# 6_Controller_A20_OUTPUT.net
KiCad netlist of a schematic drawn in Altium Designer
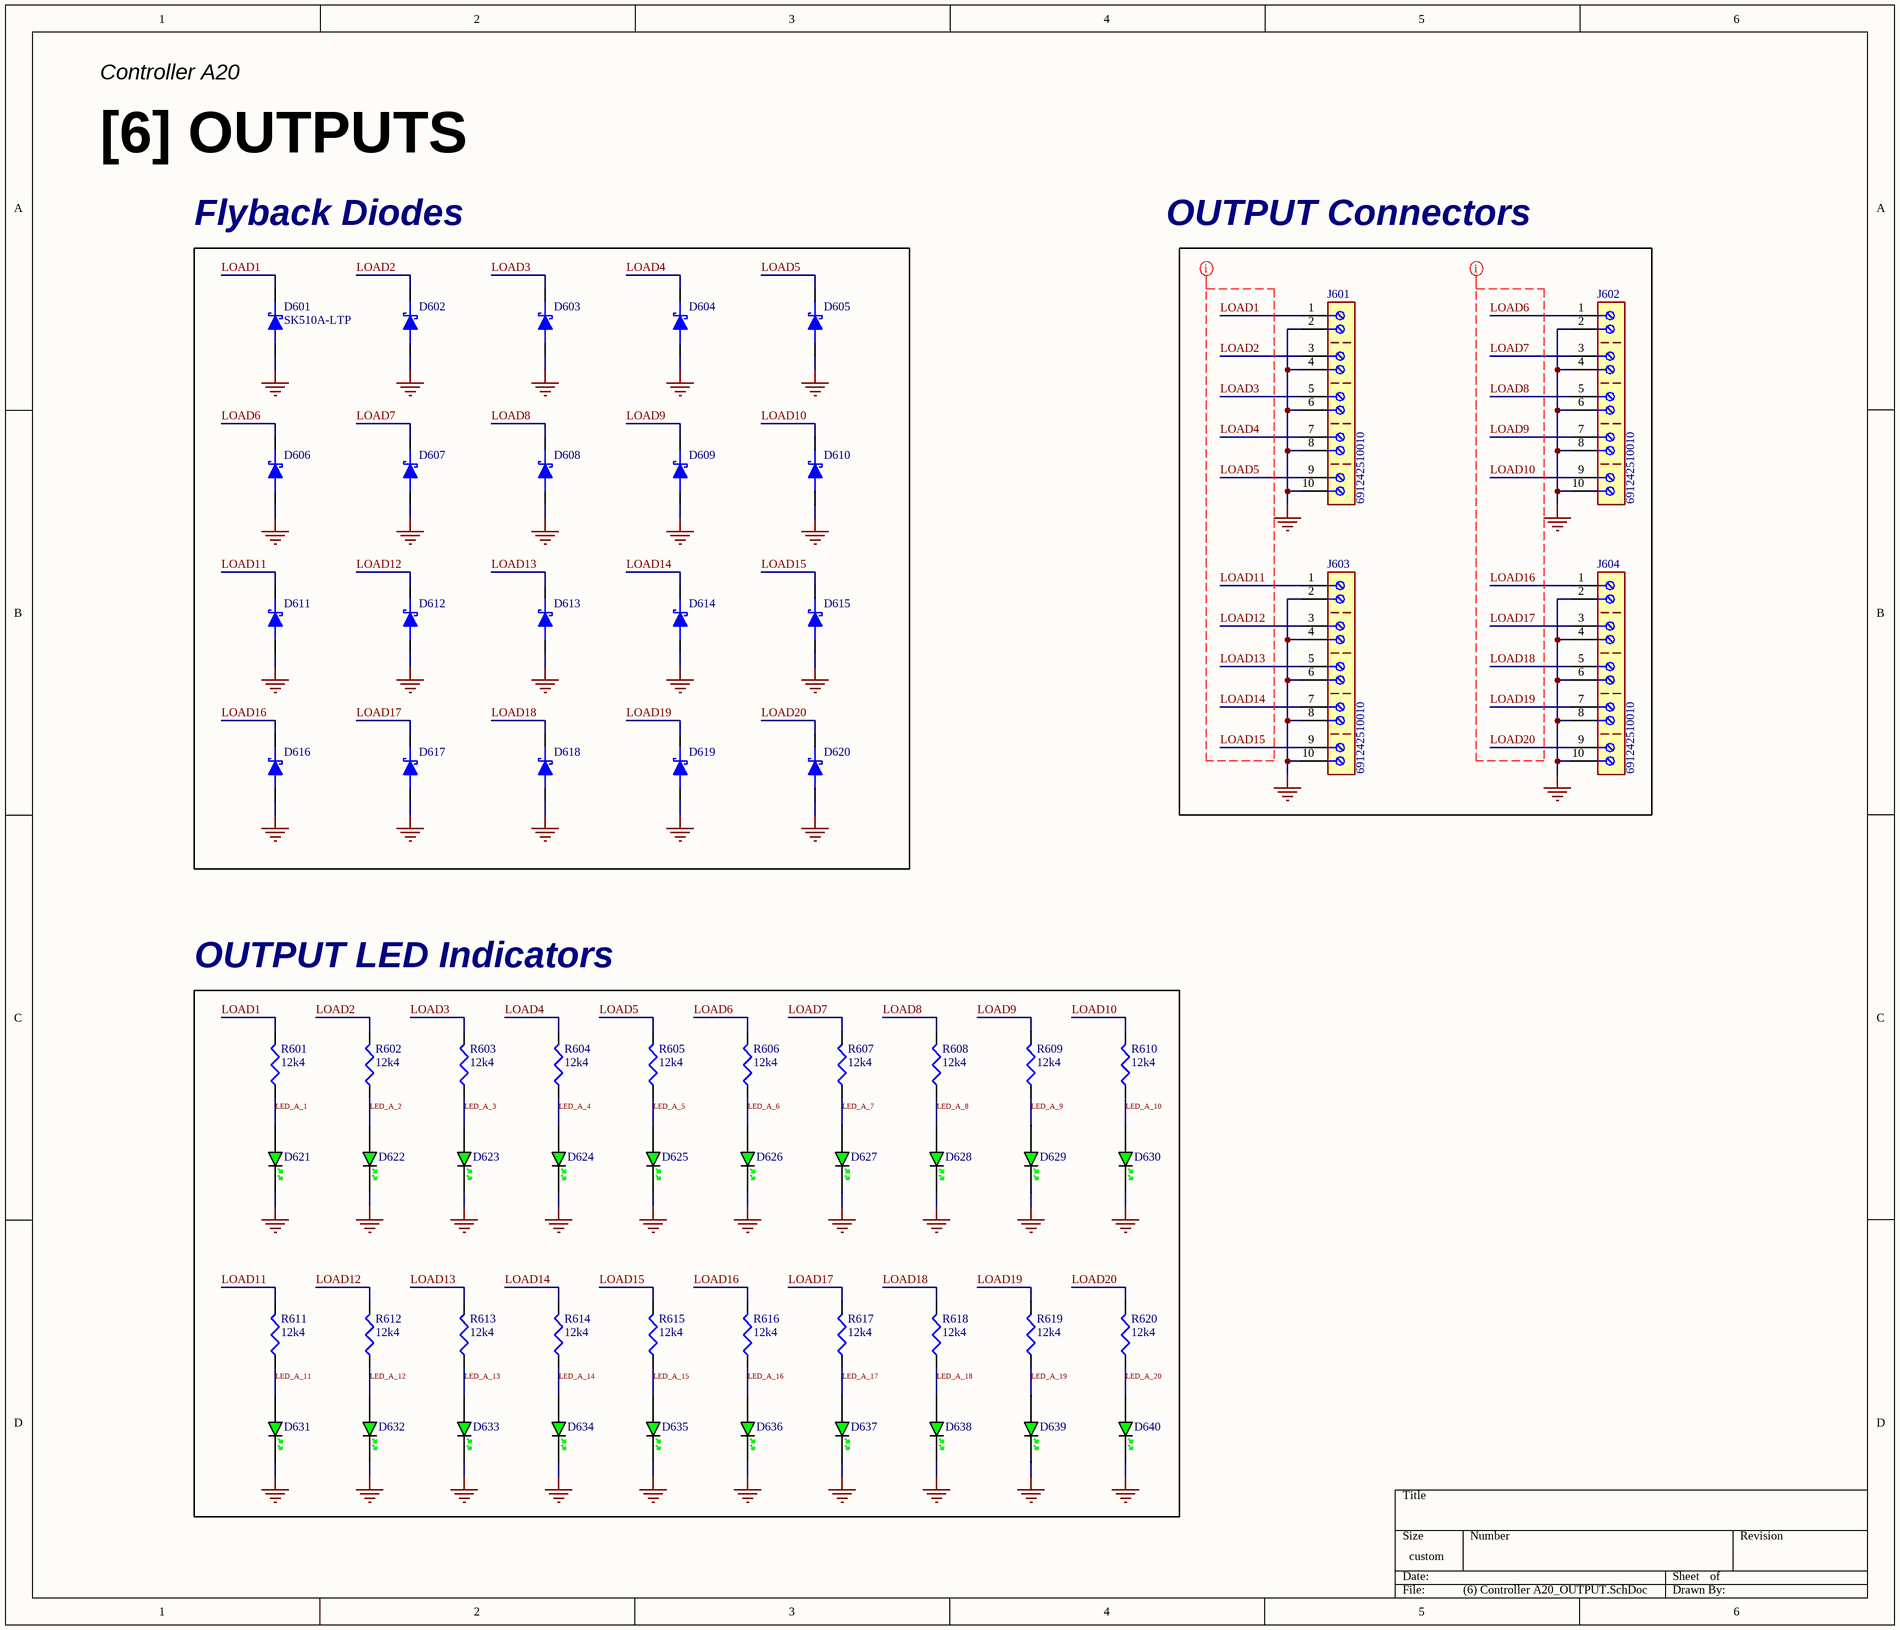
[diagram p0: (6) Controller A20_OUTPUT.SchDoc]

(export (version "E")
  (design (tool "Eeschema 10.0.6"))
  (components
    (comp (ref "D601")
      (value "SK510A-LTP")
      (footprint "DO-214AC(SMA)")
      (description "Diode 100 V 5A Surface Mount DO-214AC (SMA)")
      (fields (field (name "MANUFACTURER") "MCC (Micro Commercial Components)"))
      (libsource (lib "Symbols") (part "SK510A-LTP 100V 5A Schottky Diode"))
    )
    (comp (ref "D602")
      (value "SK510A-LTP")
      (footprint "DO-214AC(SMA)")
      (description "Diode 100 V 5A Surface Mount DO-214AC (SMA)")
      (fields (field (name "MANUFACTURER") "MCC (Micro Commercial Components)"))
      (libsource (lib "Symbols") (part "SK510A-LTP 100V 5A Schottky Diode"))
    )
    (comp (ref "D603")
      (value "SK510A-LTP")
      (footprint "DO-214AC(SMA)")
      (description "Diode 100 V 5A Surface Mount DO-214AC (SMA)")
      (fields (field (name "MANUFACTURER") "MCC (Micro Commercial Components)"))
      (libsource (lib "Symbols") (part "SK510A-LTP 100V 5A Schottky Diode"))
    )
    (comp (ref "D604")
      (value "SK510A-LTP")
      (footprint "DO-214AC(SMA)")
      (description "Diode 100 V 5A Surface Mount DO-214AC (SMA)")
      (fields (field (name "MANUFACTURER") "MCC (Micro Commercial Components)"))
      (libsource (lib "Symbols") (part "SK510A-LTP 100V 5A Schottky Diode"))
    )
    (comp (ref "D605")
      (value "SK510A-LTP")
      (footprint "DO-214AC(SMA)")
      (description "Diode 100 V 5A Surface Mount DO-214AC (SMA)")
      (fields (field (name "MANUFACTURER") "MCC (Micro Commercial Components)"))
      (libsource (lib "Symbols") (part "SK510A-LTP 100V 5A Schottky Diode"))
    )
    (comp (ref "D606")
      (value "SK510A-LTP")
      (footprint "DO-214AC(SMA)")
      (description "Diode 100 V 5A Surface Mount DO-214AC (SMA)")
      (fields (field (name "MANUFACTURER") "MCC (Micro Commercial Components)"))
      (libsource (lib "Symbols") (part "SK510A-LTP 100V 5A Schottky Diode"))
    )
    (comp (ref "D607")
      (value "SK510A-LTP")
      (footprint "DO-214AC(SMA)")
      (description "Diode 100 V 5A Surface Mount DO-214AC (SMA)")
      (fields (field (name "MANUFACTURER") "MCC (Micro Commercial Components)"))
      (libsource (lib "Symbols") (part "SK510A-LTP 100V 5A Schottky Diode"))
    )
    (comp (ref "D608")
      (value "SK510A-LTP")
      (footprint "DO-214AC(SMA)")
      (description "Diode 100 V 5A Surface Mount DO-214AC (SMA)")
      (fields (field (name "MANUFACTURER") "MCC (Micro Commercial Components)"))
      (libsource (lib "Symbols") (part "SK510A-LTP 100V 5A Schottky Diode"))
    )
    (comp (ref "D609")
      (value "SK510A-LTP")
      (footprint "DO-214AC(SMA)")
      (description "Diode 100 V 5A Surface Mount DO-214AC (SMA)")
      (fields (field (name "MANUFACTURER") "MCC (Micro Commercial Components)"))
      (libsource (lib "Symbols") (part "SK510A-LTP 100V 5A Schottky Diode"))
    )
    (comp (ref "D610")
      (value "SK510A-LTP")
      (footprint "DO-214AC(SMA)")
      (description "Diode 100 V 5A Surface Mount DO-214AC (SMA)")
      (fields (field (name "MANUFACTURER") "MCC (Micro Commercial Components)"))
      (libsource (lib "Symbols") (part "SK510A-LTP 100V 5A Schottky Diode"))
    )
    (comp (ref "D611")
      (value "SK510A-LTP")
      (footprint "DO-214AC(SMA)")
      (description "Diode 100 V 5A Surface Mount DO-214AC (SMA)")
      (fields (field (name "MANUFACTURER") "MCC (Micro Commercial Components)"))
      (libsource (lib "Symbols") (part "SK510A-LTP 100V 5A Schottky Diode"))
    )
    (comp (ref "D612")
      (value "SK510A-LTP")
      (footprint "DO-214AC(SMA)")
      (description "Diode 100 V 5A Surface Mount DO-214AC (SMA)")
      (fields (field (name "MANUFACTURER") "MCC (Micro Commercial Components)"))
      (libsource (lib "Symbols") (part "SK510A-LTP 100V 5A Schottky Diode"))
    )
    (comp (ref "D613")
      (value "SK510A-LTP")
      (footprint "DO-214AC(SMA)")
      (description "Diode 100 V 5A Surface Mount DO-214AC (SMA)")
      (fields (field (name "MANUFACTURER") "MCC (Micro Commercial Components)"))
      (libsource (lib "Symbols") (part "SK510A-LTP 100V 5A Schottky Diode"))
    )
    (comp (ref "D614")
      (value "SK510A-LTP")
      (footprint "DO-214AC(SMA)")
      (description "Diode 100 V 5A Surface Mount DO-214AC (SMA)")
      (fields (field (name "MANUFACTURER") "MCC (Micro Commercial Components)"))
      (libsource (lib "Symbols") (part "SK510A-LTP 100V 5A Schottky Diode"))
    )
    (comp (ref "D615")
      (value "SK510A-LTP")
      (footprint "DO-214AC(SMA)")
      (description "Diode 100 V 5A Surface Mount DO-214AC (SMA)")
      (fields (field (name "MANUFACTURER") "MCC (Micro Commercial Components)"))
      (libsource (lib "Symbols") (part "SK510A-LTP 100V 5A Schottky Diode"))
    )
    (comp (ref "D616")
      (value "SK510A-LTP")
      (footprint "DO-214AC(SMA)")
      (description "Diode 100 V 5A Surface Mount DO-214AC (SMA)")
      (fields (field (name "MANUFACTURER") "MCC (Micro Commercial Components)"))
      (libsource (lib "Symbols") (part "SK510A-LTP 100V 5A Schottky Diode"))
    )
    (comp (ref "D617")
      (value "SK510A-LTP")
      (footprint "DO-214AC(SMA)")
      (description "Diode 100 V 5A Surface Mount DO-214AC (SMA)")
      (fields (field (name "MANUFACTURER") "MCC (Micro Commercial Components)"))
      (libsource (lib "Symbols") (part "SK510A-LTP 100V 5A Schottky Diode"))
    )
    (comp (ref "D618")
      (value "SK510A-LTP")
      (footprint "DO-214AC(SMA)")
      (description "Diode 100 V 5A Surface Mount DO-214AC (SMA)")
      (fields (field (name "MANUFACTURER") "MCC (Micro Commercial Components)"))
      (libsource (lib "Symbols") (part "SK510A-LTP 100V 5A Schottky Diode"))
    )
    (comp (ref "D619")
      (value "SK510A-LTP")
      (footprint "DO-214AC(SMA)")
      (description "Diode 100 V 5A Surface Mount DO-214AC (SMA)")
      (fields (field (name "MANUFACTURER") "MCC (Micro Commercial Components)"))
      (libsource (lib "Symbols") (part "SK510A-LTP 100V 5A Schottky Diode"))
    )
    (comp (ref "D620")
      (value "SK510A-LTP")
      (footprint "DO-214AC(SMA)")
      (description "Diode 100 V 5A Surface Mount DO-214AC (SMA)")
      (fields (field (name "MANUFACTURER") "MCC (Micro Commercial Components)"))
      (libsource (lib "Symbols") (part "SK510A-LTP 100V 5A Schottky Diode"))
    )
    (comp (ref "D621")
      (value "XL-2012UGC")
      (footprint "0805 G LED")
      (description "Green 525nm LED Indication - Discrete 2.9V 0805 (2012 Metric)")
      (fields (field (name "MANUFACTURER") "XINGLIGHT"))
      (libsource (lib "Symbols") (part "LED EMERALD"))
    )
    (comp (ref "D622")
      (value "XL-2012UGC")
      (footprint "0805 G LED")
      (description "Green 525nm LED Indication - Discrete 2.9V 0805 (2012 Metric)")
      (fields (field (name "MANUFACTURER") "XINGLIGHT"))
      (libsource (lib "Symbols") (part "LED EMERALD"))
    )
    (comp (ref "D623")
      (value "XL-2012UGC")
      (footprint "0805 G LED")
      (description "Green 525nm LED Indication - Discrete 2.9V 0805 (2012 Metric)")
      (fields (field (name "MANUFACTURER") "XINGLIGHT"))
      (libsource (lib "Symbols") (part "LED EMERALD"))
    )
    (comp (ref "D624")
      (value "XL-2012UGC")
      (footprint "0805 G LED")
      (description "Green 525nm LED Indication - Discrete 2.9V 0805 (2012 Metric)")
      (fields (field (name "MANUFACTURER") "XINGLIGHT"))
      (libsource (lib "Symbols") (part "LED EMERALD"))
    )
    (comp (ref "D625")
      (value "XL-2012UGC")
      (footprint "0805 G LED")
      (description "Green 525nm LED Indication - Discrete 2.9V 0805 (2012 Metric)")
      (fields (field (name "MANUFACTURER") "XINGLIGHT"))
      (libsource (lib "Symbols") (part "LED EMERALD"))
    )
    (comp (ref "D626")
      (value "XL-2012UGC")
      (footprint "0805 G LED")
      (description "Green 525nm LED Indication - Discrete 2.9V 0805 (2012 Metric)")
      (fields (field (name "MANUFACTURER") "XINGLIGHT"))
      (libsource (lib "Symbols") (part "LED EMERALD"))
    )
    (comp (ref "D627")
      (value "XL-2012UGC")
      (footprint "0805 G LED")
      (description "Green 525nm LED Indication - Discrete 2.9V 0805 (2012 Metric)")
      (fields (field (name "MANUFACTURER") "XINGLIGHT"))
      (libsource (lib "Symbols") (part "LED EMERALD"))
    )
    (comp (ref "D628")
      (value "XL-2012UGC")
      (footprint "0805 G LED")
      (description "Green 525nm LED Indication - Discrete 2.9V 0805 (2012 Metric)")
      (fields (field (name "MANUFACTURER") "XINGLIGHT"))
      (libsource (lib "Symbols") (part "LED EMERALD"))
    )
    (comp (ref "D629")
      (value "XL-2012UGC")
      (footprint "0805 G LED")
      (description "Green 525nm LED Indication - Discrete 2.9V 0805 (2012 Metric)")
      (fields (field (name "MANUFACTURER") "XINGLIGHT"))
      (libsource (lib "Symbols") (part "LED EMERALD"))
    )
    (comp (ref "D630")
      (value "XL-2012UGC")
      (footprint "0805 G LED")
      (description "Green 525nm LED Indication - Discrete 2.9V 0805 (2012 Metric)")
      (fields (field (name "MANUFACTURER") "XINGLIGHT"))
      (libsource (lib "Symbols") (part "LED EMERALD"))
    )
    (comp (ref "D631")
      (value "XL-2012UGC")
      (footprint "0805 G LED")
      (description "Green 525nm LED Indication - Discrete 2.9V 0805 (2012 Metric)")
      (fields (field (name "MANUFACTURER") "XINGLIGHT"))
      (libsource (lib "Symbols") (part "LED EMERALD"))
    )
    (comp (ref "D632")
      (value "XL-2012UGC")
      (footprint "0805 G LED")
      (description "Green 525nm LED Indication - Discrete 2.9V 0805 (2012 Metric)")
      (fields (field (name "MANUFACTURER") "XINGLIGHT"))
      (libsource (lib "Symbols") (part "LED EMERALD"))
    )
    (comp (ref "D633")
      (value "XL-2012UGC")
      (footprint "0805 G LED")
      (description "Green 525nm LED Indication - Discrete 2.9V 0805 (2012 Metric)")
      (fields (field (name "MANUFACTURER") "XINGLIGHT"))
      (libsource (lib "Symbols") (part "LED EMERALD"))
    )
    (comp (ref "D634")
      (value "XL-2012UGC")
      (footprint "0805 G LED")
      (description "Green 525nm LED Indication - Discrete 2.9V 0805 (2012 Metric)")
      (fields (field (name "MANUFACTURER") "XINGLIGHT"))
      (libsource (lib "Symbols") (part "LED EMERALD"))
    )
    (comp (ref "D635")
      (value "XL-2012UGC")
      (footprint "0805 G LED")
      (description "Green 525nm LED Indication - Discrete 2.9V 0805 (2012 Metric)")
      (fields (field (name "MANUFACTURER") "XINGLIGHT"))
      (libsource (lib "Symbols") (part "LED EMERALD"))
    )
    (comp (ref "D636")
      (value "XL-2012UGC")
      (footprint "0805 G LED")
      (description "Green 525nm LED Indication - Discrete 2.9V 0805 (2012 Metric)")
      (fields (field (name "MANUFACTURER") "XINGLIGHT"))
      (libsource (lib "Symbols") (part "LED EMERALD"))
    )
    (comp (ref "D637")
      (value "XL-2012UGC")
      (footprint "0805 G LED")
      (description "Green 525nm LED Indication - Discrete 2.9V 0805 (2012 Metric)")
      (fields (field (name "MANUFACTURER") "XINGLIGHT"))
      (libsource (lib "Symbols") (part "LED EMERALD"))
    )
    (comp (ref "D638")
      (value "XL-2012UGC")
      (footprint "0805 G LED")
      (description "Green 525nm LED Indication - Discrete 2.9V 0805 (2012 Metric)")
      (fields (field (name "MANUFACTURER") "XINGLIGHT"))
      (libsource (lib "Symbols") (part "LED EMERALD"))
    )
    (comp (ref "D639")
      (value "XL-2012UGC")
      (footprint "0805 G LED")
      (description "Green 525nm LED Indication - Discrete 2.9V 0805 (2012 Metric)")
      (fields (field (name "MANUFACTURER") "XINGLIGHT"))
      (libsource (lib "Symbols") (part "LED EMERALD"))
    )
    (comp (ref "D640")
      (value "XL-2012UGC")
      (footprint "0805 G LED")
      (description "Green 525nm LED Indication - Discrete 2.9V 0805 (2012 Metric)")
      (fields (field (name "MANUFACTURER") "XINGLIGHT"))
      (libsource (lib "Symbols") (part "LED EMERALD"))
    )
    (comp (ref "J601")
      (value "691242510010")
      (footprint "5.08mm 10P STB")
      (description "10 Position Wire to Board Terminal Block Horizontal with Board 0.200\" (5.08mm) Through Hole")
      (fields (field (name "MANUFACTURER") "Würth Elektronik"))
      (libsource (lib "Symbols") (part "Terminal Block 10P 14A"))
    )
    (comp (ref "J602")
      (value "691242510010")
      (footprint "5.08mm 10P STB")
      (description "10 Position Wire to Board Terminal Block Horizontal with Board 0.200\" (5.08mm) Through Hole")
      (fields (field (name "MANUFACTURER") "Würth Elektronik"))
      (libsource (lib "Symbols") (part "Terminal Block 10P 14A"))
    )
    (comp (ref "J603")
      (value "691242510010")
      (footprint "5.08mm 10P STB")
      (description "10 Position Wire to Board Terminal Block Horizontal with Board 0.200\" (5.08mm) Through Hole")
      (fields (field (name "MANUFACTURER") "Würth Elektronik"))
      (libsource (lib "Symbols") (part "Terminal Block 10P 14A"))
    )
    (comp (ref "J604")
      (value "691242510010")
      (footprint "5.08mm 10P STB")
      (description "10 Position Wire to Board Terminal Block Horizontal with Board 0.200\" (5.08mm) Through Hole")
      (fields (field (name "MANUFACTURER") "Würth Elektronik"))
      (libsource (lib "Symbols") (part "Terminal Block 10P 14A"))
    )
    (comp (ref "R601")
      (value "12k4")
      (footprint "R0603")
      (description "12.4 kOhms ±1% 0.1W, 1/10W Chip Resistor 0603 (1608 Metric) Moisture Resistant Thick Film")
      (fields (field (name "MANUFACTURER") "YAGEO") (field (name "MFR. PART #") "RC0603FR-0712K4L"))
      (libsource (lib "Symbols") (part "RES 12.4k"))
    )
    (comp (ref "R602")
      (value "12k4")
      (footprint "R0603")
      (description "12.4 kOhms ±1% 0.1W, 1/10W Chip Resistor 0603 (1608 Metric) Moisture Resistant Thick Film")
      (fields (field (name "MANUFACTURER") "YAGEO") (field (name "MFR. PART #") "RC0603FR-0712K4L"))
      (libsource (lib "Symbols") (part "RES 12.4k"))
    )
    (comp (ref "R603")
      (value "12k4")
      (footprint "R0603")
      (description "12.4 kOhms ±1% 0.1W, 1/10W Chip Resistor 0603 (1608 Metric) Moisture Resistant Thick Film")
      (fields (field (name "MANUFACTURER") "YAGEO") (field (name "MFR. PART #") "RC0603FR-0712K4L"))
      (libsource (lib "Symbols") (part "RES 12.4k"))
    )
    (comp (ref "R604")
      (value "12k4")
      (footprint "R0603")
      (description "12.4 kOhms ±1% 0.1W, 1/10W Chip Resistor 0603 (1608 Metric) Moisture Resistant Thick Film")
      (fields (field (name "MANUFACTURER") "YAGEO") (field (name "MFR. PART #") "RC0603FR-0712K4L"))
      (libsource (lib "Symbols") (part "RES 12.4k"))
    )
    (comp (ref "R605")
      (value "12k4")
      (footprint "R0603")
      (description "12.4 kOhms ±1% 0.1W, 1/10W Chip Resistor 0603 (1608 Metric) Moisture Resistant Thick Film")
      (fields (field (name "MANUFACTURER") "YAGEO") (field (name "MFR. PART #") "RC0603FR-0712K4L"))
      (libsource (lib "Symbols") (part "RES 12.4k"))
    )
    (comp (ref "R606")
      (value "12k4")
      (footprint "R0603")
      (description "12.4 kOhms ±1% 0.1W, 1/10W Chip Resistor 0603 (1608 Metric) Moisture Resistant Thick Film")
      (fields (field (name "MANUFACTURER") "YAGEO") (field (name "MFR. PART #") "RC0603FR-0712K4L"))
      (libsource (lib "Symbols") (part "RES 12.4k"))
    )
    (comp (ref "R607")
      (value "12k4")
      (footprint "R0603")
      (description "12.4 kOhms ±1% 0.1W, 1/10W Chip Resistor 0603 (1608 Metric) Moisture Resistant Thick Film")
      (fields (field (name "MANUFACTURER") "YAGEO") (field (name "MFR. PART #") "RC0603FR-0712K4L"))
      (libsource (lib "Symbols") (part "RES 12.4k"))
    )
    (comp (ref "R608")
      (value "12k4")
      (footprint "R0603")
      (description "12.4 kOhms ±1% 0.1W, 1/10W Chip Resistor 0603 (1608 Metric) Moisture Resistant Thick Film")
      (fields (field (name "MANUFACTURER") "YAGEO") (field (name "MFR. PART #") "RC0603FR-0712K4L"))
      (libsource (lib "Symbols") (part "RES 12.4k"))
    )
    (comp (ref "R609")
      (value "12k4")
      (footprint "R0603")
      (description "12.4 kOhms ±1% 0.1W, 1/10W Chip Resistor 0603 (1608 Metric) Moisture Resistant Thick Film")
      (fields (field (name "MANUFACTURER") "YAGEO") (field (name "MFR. PART #") "RC0603FR-0712K4L"))
      (libsource (lib "Symbols") (part "RES 12.4k"))
    )
    (comp (ref "R610")
      (value "12k4")
      (footprint "R0603")
      (description "12.4 kOhms ±1% 0.1W, 1/10W Chip Resistor 0603 (1608 Metric) Moisture Resistant Thick Film")
      (fields (field (name "MANUFACTURER") "YAGEO") (field (name "MFR. PART #") "RC0603FR-0712K4L"))
      (libsource (lib "Symbols") (part "RES 12.4k"))
    )
    (comp (ref "R611")
      (value "12k4")
      (footprint "R0603")
      (description "12.4 kOhms ±1% 0.1W, 1/10W Chip Resistor 0603 (1608 Metric) Moisture Resistant Thick Film")
      (fields (field (name "MANUFACTURER") "YAGEO") (field (name "MFR. PART #") "RC0603FR-0712K4L"))
      (libsource (lib "Symbols") (part "RES 12.4k"))
    )
    (comp (ref "R612")
      (value "12k4")
      (footprint "R0603")
      (description "12.4 kOhms ±1% 0.1W, 1/10W Chip Resistor 0603 (1608 Metric) Moisture Resistant Thick Film")
      (fields (field (name "MANUFACTURER") "YAGEO") (field (name "MFR. PART #") "RC0603FR-0712K4L"))
      (libsource (lib "Symbols") (part "RES 12.4k"))
    )
    (comp (ref "R613")
      (value "12k4")
      (footprint "R0603")
      (description "12.4 kOhms ±1% 0.1W, 1/10W Chip Resistor 0603 (1608 Metric) Moisture Resistant Thick Film")
      (fields (field (name "MANUFACTURER") "YAGEO") (field (name "MFR. PART #") "RC0603FR-0712K4L"))
      (libsource (lib "Symbols") (part "RES 12.4k"))
    )
    (comp (ref "R614")
      (value "12k4")
      (footprint "R0603")
      (description "12.4 kOhms ±1% 0.1W, 1/10W Chip Resistor 0603 (1608 Metric) Moisture Resistant Thick Film")
      (fields (field (name "MANUFACTURER") "YAGEO") (field (name "MFR. PART #") "RC0603FR-0712K4L"))
      (libsource (lib "Symbols") (part "RES 12.4k"))
    )
    (comp (ref "R615")
      (value "12k4")
      (footprint "R0603")
      (description "12.4 kOhms ±1% 0.1W, 1/10W Chip Resistor 0603 (1608 Metric) Moisture Resistant Thick Film")
      (fields (field (name "MANUFACTURER") "YAGEO") (field (name "MFR. PART #") "RC0603FR-0712K4L"))
      (libsource (lib "Symbols") (part "RES 12.4k"))
    )
    (comp (ref "R616")
      (value "12k4")
      (footprint "R0603")
      (description "12.4 kOhms ±1% 0.1W, 1/10W Chip Resistor 0603 (1608 Metric) Moisture Resistant Thick Film")
      (fields (field (name "MANUFACTURER") "YAGEO") (field (name "MFR. PART #") "RC0603FR-0712K4L"))
      (libsource (lib "Symbols") (part "RES 12.4k"))
    )
    (comp (ref "R617")
      (value "12k4")
      (footprint "R0603")
      (description "12.4 kOhms ±1% 0.1W, 1/10W Chip Resistor 0603 (1608 Metric) Moisture Resistant Thick Film")
      (fields (field (name "MANUFACTURER") "YAGEO") (field (name "MFR. PART #") "RC0603FR-0712K4L"))
      (libsource (lib "Symbols") (part "RES 12.4k"))
    )
    (comp (ref "R618")
      (value "12k4")
      (footprint "R0603")
      (description "12.4 kOhms ±1% 0.1W, 1/10W Chip Resistor 0603 (1608 Metric) Moisture Resistant Thick Film")
      (fields (field (name "MANUFACTURER") "YAGEO") (field (name "MFR. PART #") "RC0603FR-0712K4L"))
      (libsource (lib "Symbols") (part "RES 12.4k"))
    )
    (comp (ref "R619")
      (value "12k4")
      (footprint "R0603")
      (description "12.4 kOhms ±1% 0.1W, 1/10W Chip Resistor 0603 (1608 Metric) Moisture Resistant Thick Film")
      (fields (field (name "MANUFACTURER") "YAGEO") (field (name "MFR. PART #") "RC0603FR-0712K4L"))
      (libsource (lib "Symbols") (part "RES 12.4k"))
    )
    (comp (ref "R620")
      (value "12k4")
      (footprint "R0603")
      (description "12.4 kOhms ±1% 0.1W, 1/10W Chip Resistor 0603 (1608 Metric) Moisture Resistant Thick Film")
      (fields (field (name "MANUFACTURER") "YAGEO") (field (name "MFR. PART #") "RC0603FR-0712K4L"))
      (libsource (lib "Symbols") (part "RES 12.4k"))
    )
  )
  (nets
    (net (code "1") (name "/LED_A_1") (class "Default")
      (node (ref "D621") (pin "1") (pinfunction "1_1") (pintype "passive"))
      (node (ref "R601") (pin "1") (pinfunction "1_1") (pintype "passive"))
    )
    (net (code "2") (name "/LED_A_2") (class "Default")
      (node (ref "D622") (pin "1") (pinfunction "1_1") (pintype "passive"))
      (node (ref "R602") (pin "1") (pinfunction "1_1") (pintype "passive"))
    )
    (net (code "3") (name "/LED_A_3") (class "Default")
      (node (ref "D623") (pin "1") (pinfunction "1_1") (pintype "passive"))
      (node (ref "R603") (pin "1") (pinfunction "1_1") (pintype "passive"))
    )
    (net (code "4") (name "/LED_A_4") (class "Default")
      (node (ref "D624") (pin "1") (pinfunction "1_1") (pintype "passive"))
      (node (ref "R604") (pin "1") (pinfunction "1_1") (pintype "passive"))
    )
    (net (code "5") (name "/LED_A_5") (class "Default")
      (node (ref "D625") (pin "1") (pinfunction "1_1") (pintype "passive"))
      (node (ref "R605") (pin "1") (pinfunction "1_1") (pintype "passive"))
    )
    (net (code "6") (name "/LED_A_6") (class "Default")
      (node (ref "D626") (pin "1") (pinfunction "1_1") (pintype "passive"))
      (node (ref "R606") (pin "1") (pinfunction "1_1") (pintype "passive"))
    )
    (net (code "7") (name "/LED_A_7") (class "Default")
      (node (ref "D627") (pin "1") (pinfunction "1_1") (pintype "passive"))
      (node (ref "R607") (pin "1") (pinfunction "1_1") (pintype "passive"))
    )
    (net (code "8") (name "/LED_A_8") (class "Default")
      (node (ref "D628") (pin "1") (pinfunction "1_1") (pintype "passive"))
      (node (ref "R608") (pin "1") (pinfunction "1_1") (pintype "passive"))
    )
    (net (code "9") (name "/LED_A_9") (class "Default")
      (node (ref "D629") (pin "1") (pinfunction "1_1") (pintype "passive"))
      (node (ref "R609") (pin "1") (pinfunction "1_1") (pintype "passive"))
    )
    (net (code "10") (name "/LED_A_10") (class "Default")
      (node (ref "D630") (pin "1") (pinfunction "1_1") (pintype "passive"))
      (node (ref "R610") (pin "1") (pinfunction "1_1") (pintype "passive"))
    )
    (net (code "11") (name "/LED_A_11") (class "Default")
      (node (ref "D631") (pin "1") (pinfunction "1_1") (pintype "passive"))
      (node (ref "R611") (pin "1") (pinfunction "1_1") (pintype "passive"))
    )
    (net (code "12") (name "/LED_A_12") (class "Default")
      (node (ref "D632") (pin "1") (pinfunction "1_1") (pintype "passive"))
      (node (ref "R612") (pin "1") (pinfunction "1_1") (pintype "passive"))
    )
    (net (code "13") (name "/LED_A_13") (class "Default")
      (node (ref "D633") (pin "1") (pinfunction "1_1") (pintype "passive"))
      (node (ref "R613") (pin "1") (pinfunction "1_1") (pintype "passive"))
    )
    (net (code "14") (name "/LED_A_14") (class "Default")
      (node (ref "D634") (pin "1") (pinfunction "1_1") (pintype "passive"))
      (node (ref "R614") (pin "1") (pinfunction "1_1") (pintype "passive"))
    )
    (net (code "15") (name "/LED_A_15") (class "Default")
      (node (ref "D635") (pin "1") (pinfunction "1_1") (pintype "passive"))
      (node (ref "R615") (pin "1") (pinfunction "1_1") (pintype "passive"))
    )
    (net (code "16") (name "/LED_A_16") (class "Default")
      (node (ref "D636") (pin "1") (pinfunction "1_1") (pintype "passive"))
      (node (ref "R616") (pin "1") (pinfunction "1_1") (pintype "passive"))
    )
    (net (code "17") (name "/LED_A_17") (class "Default")
      (node (ref "D637") (pin "1") (pinfunction "1_1") (pintype "passive"))
      (node (ref "R617") (pin "1") (pinfunction "1_1") (pintype "passive"))
    )
    (net (code "18") (name "/LED_A_18") (class "Default")
      (node (ref "D638") (pin "1") (pinfunction "1_1") (pintype "passive"))
      (node (ref "R618") (pin "1") (pinfunction "1_1") (pintype "passive"))
    )
    (net (code "19") (name "/LED_A_19") (class "Default")
      (node (ref "D639") (pin "1") (pinfunction "1_1") (pintype "passive"))
      (node (ref "R619") (pin "1") (pinfunction "1_1") (pintype "passive"))
    )
    (net (code "20") (name "/LED_A_20") (class "Default")
      (node (ref "D640") (pin "1") (pinfunction "1_1") (pintype "passive"))
      (node (ref "R620") (pin "1") (pinfunction "1_1") (pintype "passive"))
    )
    (net (code "21") (name "/LOAD1") (class "Default")
      (node (ref "D601") (pin "2") (pinfunction "2_2") (pintype "passive"))
      (node (ref "J601") (pin "1") (pinfunction "1_1") (pintype "passive"))
      (node (ref "R601") (pin "2") (pinfunction "2_2") (pintype "passive"))
    )
    (net (code "22") (name "/LOAD2") (class "Default")
      (node (ref "D602") (pin "2") (pinfunction "2_2") (pintype "passive"))
      (node (ref "J601") (pin "3") (pinfunction "3_3") (pintype "passive"))
      (node (ref "R602") (pin "2") (pinfunction "2_2") (pintype "passive"))
    )
    (net (code "23") (name "/LOAD3") (class "Default")
      (node (ref "D603") (pin "2") (pinfunction "2_2") (pintype "passive"))
      (node (ref "J601") (pin "5") (pinfunction "5_5") (pintype "passive"))
      (node (ref "R603") (pin "2") (pinfunction "2_2") (pintype "passive"))
    )
    (net (code "24") (name "/LOAD4") (class "Default")
      (node (ref "D604") (pin "2") (pinfunction "2_2") (pintype "passive"))
      (node (ref "J601") (pin "7") (pinfunction "7_7") (pintype "passive"))
      (node (ref "R604") (pin "2") (pinfunction "2_2") (pintype "passive"))
    )
    (net (code "25") (name "/LOAD5") (class "Default")
      (node (ref "D605") (pin "2") (pinfunction "2_2") (pintype "passive"))
      (node (ref "J601") (pin "9") (pinfunction "9_9") (pintype "passive"))
      (node (ref "R605") (pin "2") (pinfunction "2_2") (pintype "passive"))
    )
    (net (code "26") (name "/LOAD6") (class "Default")
      (node (ref "D606") (pin "2") (pinfunction "2_2") (pintype "passive"))
      (node (ref "J602") (pin "1") (pinfunction "1_1") (pintype "passive"))
      (node (ref "R606") (pin "2") (pinfunction "2_2") (pintype "passive"))
    )
    (net (code "27") (name "/LOAD7") (class "Default")
      (node (ref "D607") (pin "2") (pinfunction "2_2") (pintype "passive"))
      (node (ref "J602") (pin "3") (pinfunction "3_3") (pintype "passive"))
      (node (ref "R607") (pin "2") (pinfunction "2_2") (pintype "passive"))
    )
    (net (code "28") (name "/LOAD8") (class "Default")
      (node (ref "D608") (pin "2") (pinfunction "2_2") (pintype "passive"))
      (node (ref "J602") (pin "5") (pinfunction "5_5") (pintype "passive"))
      (node (ref "R608") (pin "2") (pinfunction "2_2") (pintype "passive"))
    )
    (net (code "29") (name "/LOAD9") (class "Default")
      (node (ref "D609") (pin "2") (pinfunction "2_2") (pintype "passive"))
      (node (ref "J602") (pin "7") (pinfunction "7_7") (pintype "passive"))
      (node (ref "R609") (pin "2") (pinfunction "2_2") (pintype "passive"))
    )
    (net (code "30") (name "/LOAD10") (class "Default")
      (node (ref "D610") (pin "2") (pinfunction "2_2") (pintype "passive"))
      (node (ref "J602") (pin "9") (pinfunction "9_9") (pintype "passive"))
      (node (ref "R610") (pin "2") (pinfunction "2_2") (pintype "passive"))
    )
    (net (code "31") (name "/LOAD11") (class "Default")
      (node (ref "D611") (pin "2") (pinfunction "2_2") (pintype "passive"))
      (node (ref "J603") (pin "1") (pinfunction "1_1") (pintype "passive"))
      (node (ref "R611") (pin "2") (pinfunction "2_2") (pintype "passive"))
    )
    (net (code "32") (name "/LOAD12") (class "Default")
      (node (ref "D612") (pin "2") (pinfunction "2_2") (pintype "passive"))
      (node (ref "J603") (pin "3") (pinfunction "3_3") (pintype "passive"))
      (node (ref "R612") (pin "2") (pinfunction "2_2") (pintype "passive"))
    )
    (net (code "33") (name "/LOAD13") (class "Default")
      (node (ref "D613") (pin "2") (pinfunction "2_2") (pintype "passive"))
      (node (ref "J603") (pin "5") (pinfunction "5_5") (pintype "passive"))
      (node (ref "R613") (pin "2") (pinfunction "2_2") (pintype "passive"))
    )
    (net (code "34") (name "/LOAD14") (class "Default")
      (node (ref "D614") (pin "2") (pinfunction "2_2") (pintype "passive"))
      (node (ref "J603") (pin "7") (pinfunction "7_7") (pintype "passive"))
      (node (ref "R614") (pin "2") (pinfunction "2_2") (pintype "passive"))
    )
    (net (code "35") (name "/LOAD15") (class "Default")
      (node (ref "D615") (pin "2") (pinfunction "2_2") (pintype "passive"))
      (node (ref "J603") (pin "9") (pinfunction "9_9") (pintype "passive"))
      (node (ref "R615") (pin "2") (pinfunction "2_2") (pintype "passive"))
    )
    (net (code "36") (name "/LOAD16") (class "Default")
      (node (ref "D616") (pin "2") (pinfunction "2_2") (pintype "passive"))
      (node (ref "J604") (pin "1") (pinfunction "1_1") (pintype "passive"))
      (node (ref "R616") (pin "2") (pinfunction "2_2") (pintype "passive"))
    )
    (net (code "37") (name "/LOAD17") (class "Default")
      (node (ref "D617") (pin "2") (pinfunction "2_2") (pintype "passive"))
      (node (ref "J604") (pin "3") (pinfunction "3_3") (pintype "passive"))
      (node (ref "R617") (pin "2") (pinfunction "2_2") (pintype "passive"))
    )
    (net (code "38") (name "/LOAD18") (class "Default")
      (node (ref "D618") (pin "2") (pinfunction "2_2") (pintype "passive"))
      (node (ref "J604") (pin "5") (pinfunction "5_5") (pintype "passive"))
      (node (ref "R618") (pin "2") (pinfunction "2_2") (pintype "passive"))
    )
    (net (code "39") (name "/LOAD19") (class "Default")
      (node (ref "D619") (pin "2") (pinfunction "2_2") (pintype "passive"))
      (node (ref "J604") (pin "7") (pinfunction "7_7") (pintype "passive"))
      (node (ref "R619") (pin "2") (pinfunction "2_2") (pintype "passive"))
    )
    (net (code "40") (name "/LOAD20") (class "Default")
      (node (ref "D620") (pin "2") (pinfunction "2_2") (pintype "passive"))
      (node (ref "J604") (pin "9") (pinfunction "9_9") (pintype "passive"))
      (node (ref "R620") (pin "2") (pinfunction "2_2") (pintype "passive"))
    )
    (net (code "41") (name "GND") (class "Default")
      (node (ref "D601") (pin "1") (pinfunction "1_1") (pintype "passive"))
      (node (ref "D602") (pin "1") (pinfunction "1_1") (pintype "passive"))
      (node (ref "D603") (pin "1") (pinfunction "1_1") (pintype "passive"))
      (node (ref "D604") (pin "1") (pinfunction "1_1") (pintype "passive"))
      (node (ref "D605") (pin "1") (pinfunction "1_1") (pintype "passive"))
      (node (ref "D606") (pin "1") (pinfunction "1_1") (pintype "passive"))
      (node (ref "D607") (pin "1") (pinfunction "1_1") (pintype "passive"))
      (node (ref "D608") (pin "1") (pinfunction "1_1") (pintype "passive"))
      (node (ref "D609") (pin "1") (pinfunction "1_1") (pintype "passive"))
      (node (ref "D610") (pin "1") (pinfunction "1_1") (pintype "passive"))
      (node (ref "D611") (pin "1") (pinfunction "1_1") (pintype "passive"))
      (node (ref "D612") (pin "1") (pinfunction "1_1") (pintype "passive"))
      (node (ref "D613") (pin "1") (pinfunction "1_1") (pintype "passive"))
      (node (ref "D614") (pin "1") (pinfunction "1_1") (pintype "passive"))
      (node (ref "D615") (pin "1") (pinfunction "1_1") (pintype "passive"))
      (node (ref "D616") (pin "1") (pinfunction "1_1") (pintype "passive"))
      (node (ref "D617") (pin "1") (pinfunction "1_1") (pintype "passive"))
      (node (ref "D618") (pin "1") (pinfunction "1_1") (pintype "passive"))
      (node (ref "D619") (pin "1") (pinfunction "1_1") (pintype "passive"))
      (node (ref "D620") (pin "1") (pinfunction "1_1") (pintype "passive"))
      (node (ref "D621") (pin "2") (pinfunction "2_2") (pintype "passive"))
      (node (ref "D622") (pin "2") (pinfunction "2_2") (pintype "passive"))
      (node (ref "D623") (pin "2") (pinfunction "2_2") (pintype "passive"))
      (node (ref "D624") (pin "2") (pinfunction "2_2") (pintype "passive"))
      (node (ref "D625") (pin "2") (pinfunction "2_2") (pintype "passive"))
      (node (ref "D626") (pin "2") (pinfunction "2_2") (pintype "passive"))
      (node (ref "D627") (pin "2") (pinfunction "2_2") (pintype "passive"))
      (node (ref "D628") (pin "2") (pinfunction "2_2") (pintype "passive"))
      (node (ref "D629") (pin "2") (pinfunction "2_2") (pintype "passive"))
      (node (ref "D630") (pin "2") (pinfunction "2_2") (pintype "passive"))
      (node (ref "D631") (pin "2") (pinfunction "2_2") (pintype "passive"))
      (node (ref "D632") (pin "2") (pinfunction "2_2") (pintype "passive"))
      (node (ref "D633") (pin "2") (pinfunction "2_2") (pintype "passive"))
      (node (ref "D634") (pin "2") (pinfunction "2_2") (pintype "passive"))
      (node (ref "D635") (pin "2") (pinfunction "2_2") (pintype "passive"))
      (node (ref "D636") (pin "2") (pinfunction "2_2") (pintype "passive"))
      (node (ref "D637") (pin "2") (pinfunction "2_2") (pintype "passive"))
      (node (ref "D638") (pin "2") (pinfunction "2_2") (pintype "passive"))
      (node (ref "D639") (pin "2") (pinfunction "2_2") (pintype "passive"))
      (node (ref "D640") (pin "2") (pinfunction "2_2") (pintype "passive"))
      (node (ref "J601") (pin "10") (pinfunction "10_10") (pintype "passive"))
      (node (ref "J601") (pin "2") (pinfunction "2_2") (pintype "passive"))
      (node (ref "J601") (pin "4") (pinfunction "4_4") (pintype "passive"))
      (node (ref "J601") (pin "6") (pinfunction "6_6") (pintype "passive"))
      (node (ref "J601") (pin "8") (pinfunction "8_8") (pintype "passive"))
      (node (ref "J602") (pin "10") (pinfunction "10_10") (pintype "passive"))
      (node (ref "J602") (pin "2") (pinfunction "2_2") (pintype "passive"))
      (node (ref "J602") (pin "4") (pinfunction "4_4") (pintype "passive"))
      (node (ref "J602") (pin "6") (pinfunction "6_6") (pintype "passive"))
      (node (ref "J602") (pin "8") (pinfunction "8_8") (pintype "passive"))
      (node (ref "J603") (pin "10") (pinfunction "10_10") (pintype "passive"))
      (node (ref "J603") (pin "2") (pinfunction "2_2") (pintype "passive"))
      (node (ref "J603") (pin "4") (pinfunction "4_4") (pintype "passive"))
      (node (ref "J603") (pin "6") (pinfunction "6_6") (pintype "passive"))
      (node (ref "J603") (pin "8") (pinfunction "8_8") (pintype "passive"))
      (node (ref "J604") (pin "10") (pinfunction "10_10") (pintype "passive"))
      (node (ref "J604") (pin "2") (pinfunction "2_2") (pintype "passive"))
      (node (ref "J604") (pin "4") (pinfunction "4_4") (pintype "passive"))
      (node (ref "J604") (pin "6") (pinfunction "6_6") (pintype "passive"))
      (node (ref "J604") (pin "8") (pinfunction "8_8") (pintype "passive"))
    )
  )
)
